# GateInterface.net
KiCad netlist of a schematic drawn in EAGLE
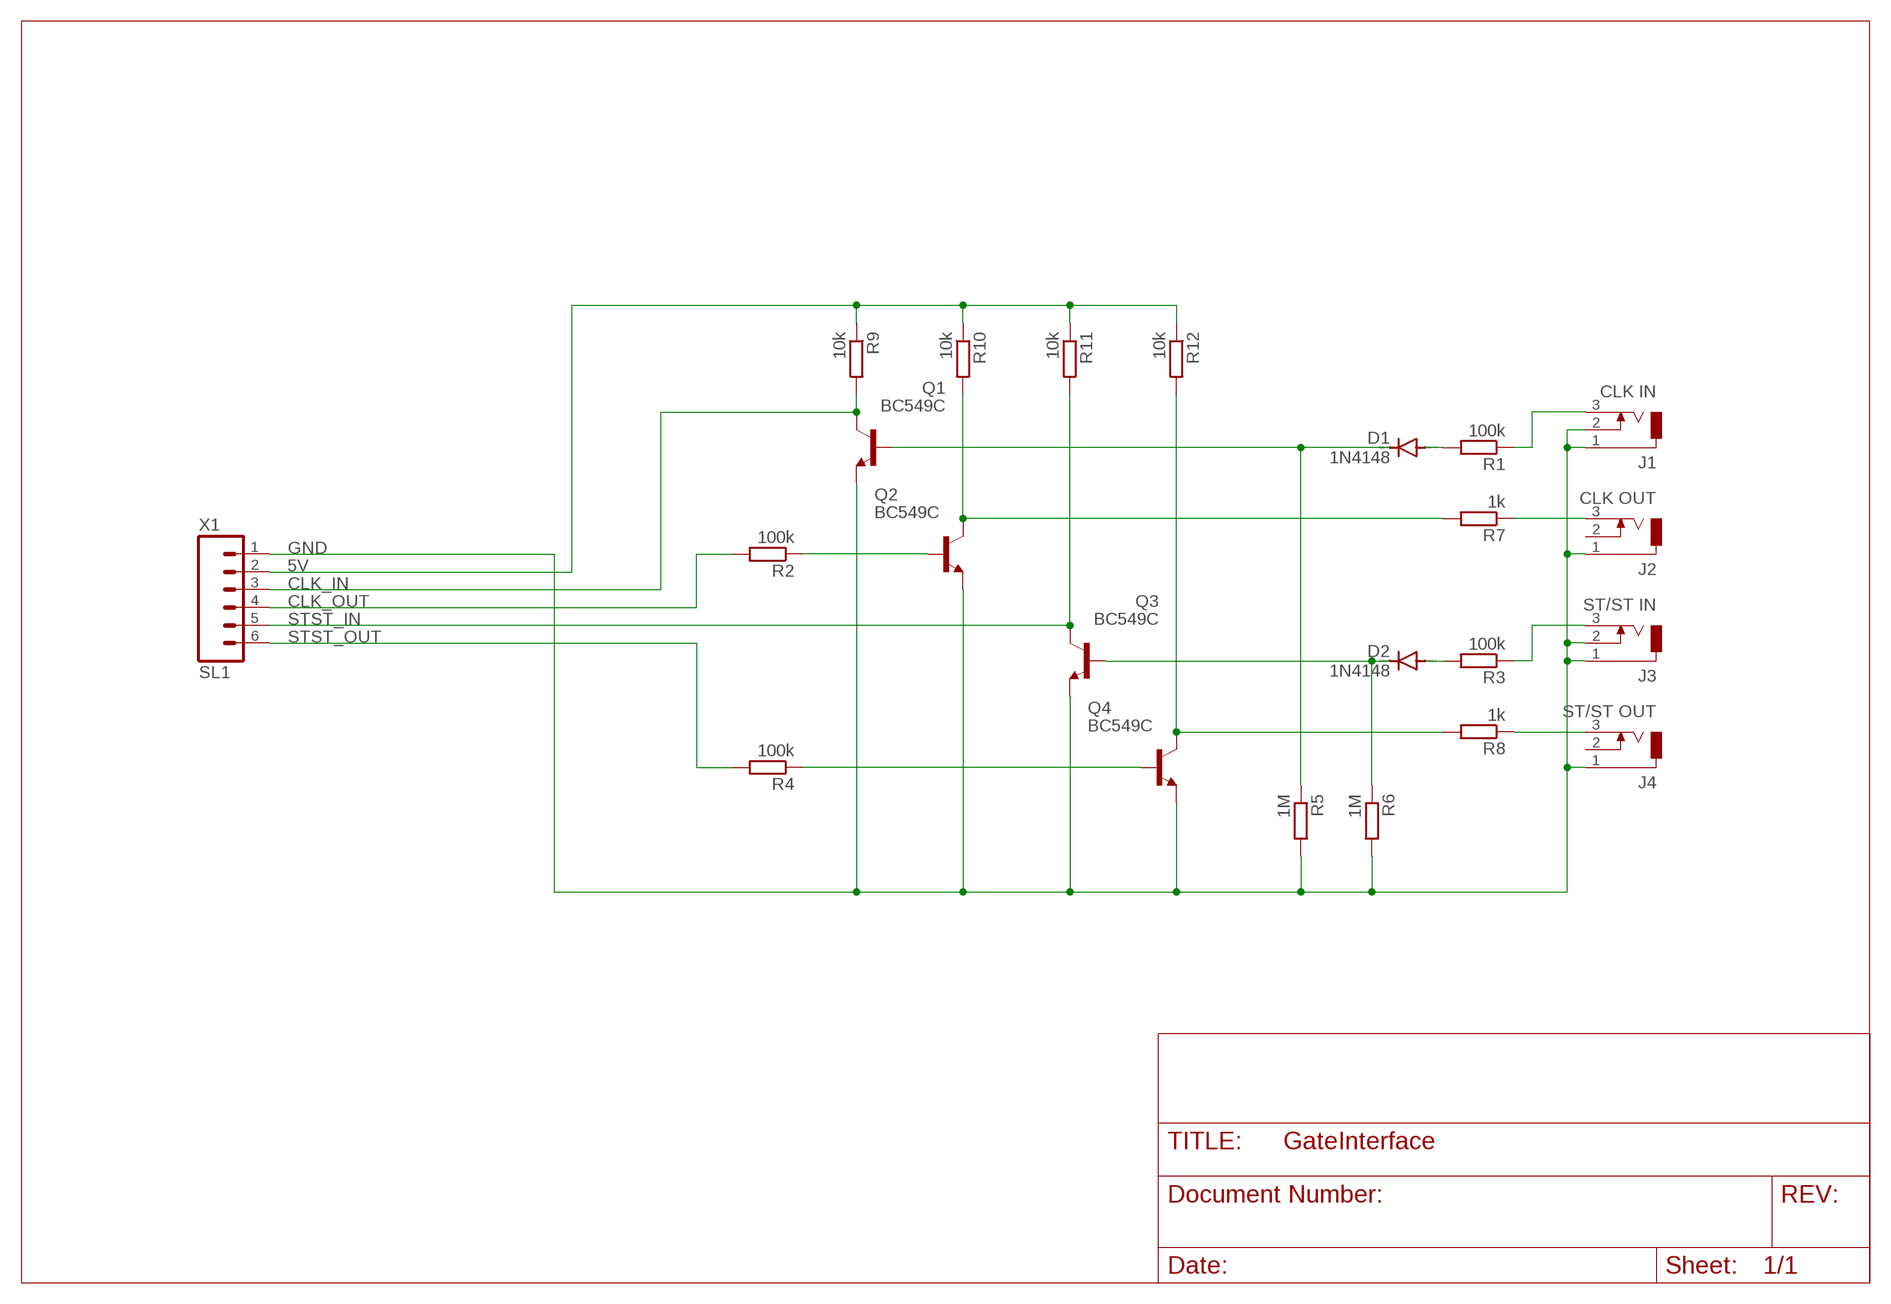
[diagram p0: schematic, sheet 1]

(export (version "E")
  (design (tool "Eeschema 10.0.6"))
  (components
    (comp (ref "D1")
      (value "1N4148")
      (footprint "eagle-import:DO35-10")
      (libsource (lib "eagle-import") (part "1N4148DO35-10"))
    )
    (comp (ref "D2")
      (value "1N4148")
      (footprint "eagle-import:DO35-10")
      (libsource (lib "eagle-import") (part "1N4148DO35-10"))
    )
    (comp (ref "J1")
      (value "CLK IN")
      (footprint "eagle-import:DCJ0202")
      (libsource (lib "eagle-import") (part "DCJ0202"))
    )
    (comp (ref "J2")
      (value "CLK OUT")
      (footprint "eagle-import:DCJ0202")
      (libsource (lib "eagle-import") (part "DCJ0202"))
    )
    (comp (ref "J3")
      (value "ST/ST IN")
      (footprint "eagle-import:DCJ0202")
      (libsource (lib "eagle-import") (part "DCJ0202"))
    )
    (comp (ref "J4")
      (value "ST/ST OUT")
      (footprint "eagle-import:DCJ0202")
      (libsource (lib "eagle-import") (part "DCJ0202"))
    )
    (comp (ref "Q1")
      (value "BC549C")
      (footprint "eagle-import:TO92-EBC")
      (libsource (lib "eagle-import") (part "BC549C"))
    )
    (comp (ref "Q2")
      (value "BC549C")
      (footprint "eagle-import:TO92-EBC")
      (libsource (lib "eagle-import") (part "BC549C"))
    )
    (comp (ref "Q3")
      (value "BC549C")
      (footprint "eagle-import:TO92-EBC")
      (libsource (lib "eagle-import") (part "BC549C"))
    )
    (comp (ref "Q4")
      (value "BC549C")
      (footprint "eagle-import:TO92-EBC")
      (libsource (lib "eagle-import") (part "BC549C"))
    )
    (comp (ref "R1")
      (value "100k")
      (footprint "eagle-import:0207_10")
      (libsource (lib "eagle-import") (part "R-EU_0207/10"))
    )
    (comp (ref "R2")
      (value "100k")
      (footprint "eagle-import:0207_10")
      (libsource (lib "eagle-import") (part "R-EU_0207/10"))
    )
    (comp (ref "R3")
      (value "100k")
      (footprint "eagle-import:0207_10")
      (libsource (lib "eagle-import") (part "R-EU_0207/10"))
    )
    (comp (ref "R4")
      (value "100k")
      (footprint "eagle-import:0207_10")
      (libsource (lib "eagle-import") (part "R-EU_0207/10"))
    )
    (comp (ref "R5")
      (value "1M")
      (footprint "eagle-import:0207_10")
      (libsource (lib "eagle-import") (part "R-EU_0207/10"))
    )
    (comp (ref "R6")
      (value "1M")
      (footprint "eagle-import:0207_10")
      (libsource (lib "eagle-import") (part "R-EU_0207/10"))
    )
    (comp (ref "R7")
      (value "1k")
      (footprint "eagle-import:0207_10")
      (libsource (lib "eagle-import") (part "R-EU_0207/10"))
    )
    (comp (ref "R8")
      (value "1k")
      (footprint "eagle-import:0207_10")
      (libsource (lib "eagle-import") (part "R-EU_0207/10"))
    )
    (comp (ref "R9")
      (value "10k")
      (footprint "eagle-import:0207_10")
      (libsource (lib "eagle-import") (part "R-EU_0207/10"))
    )
    (comp (ref "R10")
      (value "10k")
      (footprint "eagle-import:0207_10")
      (libsource (lib "eagle-import") (part "R-EU_0207/10"))
    )
    (comp (ref "R11")
      (value "10k")
      (footprint "eagle-import:0207_10")
      (libsource (lib "eagle-import") (part "R-EU_0207/10"))
    )
    (comp (ref "R12")
      (value "10k")
      (footprint "eagle-import:0207_10")
      (libsource (lib "eagle-import") (part "R-EU_0207/10"))
    )
    (comp (ref "SL1")
      (value "X1")
      (footprint "eagle-import:06P")
      (libsource (lib "eagle-import") (part "M06"))
    )
  )
  (nets
    (net (code "1") (name "/5V") (class "Default")
      (node (ref "R10") (pin "1") (pinfunction "1_1") (pintype "passive"))
      (node (ref "R11") (pin "1") (pinfunction "1_1") (pintype "passive"))
      (node (ref "R12") (pin "1") (pinfunction "1_1") (pintype "passive"))
      (node (ref "R9") (pin "1") (pinfunction "1_1") (pintype "passive"))
      (node (ref "SL1") (pin "2") (pinfunction "2_2") (pintype "passive"))
    )
    (net (code "2") (name "/CLK_IN") (class "Default")
      (node (ref "Q1") (pin "C") (pinfunction "C_C") (pintype "passive"))
      (node (ref "R9") (pin "2") (pinfunction "2_2") (pintype "passive"))
      (node (ref "SL1") (pin "3") (pinfunction "3_3") (pintype "passive"))
    )
    (net (code "3") (name "/CLK_OUT") (class "Default")
      (node (ref "R2") (pin "2") (pinfunction "2_2") (pintype "passive"))
      (node (ref "SL1") (pin "4") (pinfunction "4_4") (pintype "passive"))
    )
    (net (code "4") (name "/GND") (class "Default")
      (node (ref "J1") (pin "1") (pinfunction "1_1") (pintype "passive"))
      (node (ref "J1") (pin "2") (pinfunction "2_2") (pintype "passive"))
      (node (ref "J2") (pin "1") (pinfunction "1_1") (pintype "passive"))
      (node (ref "J3") (pin "1") (pinfunction "1_1") (pintype "passive"))
      (node (ref "J3") (pin "2") (pinfunction "2_2") (pintype "passive"))
      (node (ref "J4") (pin "1") (pinfunction "1_1") (pintype "passive"))
      (node (ref "Q1") (pin "E") (pinfunction "E_E") (pintype "passive"))
      (node (ref "Q2") (pin "E") (pinfunction "E_E") (pintype "passive"))
      (node (ref "Q3") (pin "E") (pinfunction "E_E") (pintype "passive"))
      (node (ref "Q4") (pin "E") (pinfunction "E_E") (pintype "passive"))
      (node (ref "R5") (pin "2") (pinfunction "2_2") (pintype "passive"))
      (node (ref "R6") (pin "2") (pinfunction "2_2") (pintype "passive"))
      (node (ref "SL1") (pin "1") (pinfunction "1_1") (pintype "passive"))
    )
    (net (code "5") (name "/STST_IN") (class "Default")
      (node (ref "Q3") (pin "C") (pinfunction "C_C") (pintype "passive"))
      (node (ref "R11") (pin "2") (pinfunction "2_2") (pintype "passive"))
      (node (ref "SL1") (pin "5") (pinfunction "5_5") (pintype "passive"))
    )
    (net (code "6") (name "/STST_OUT") (class "Default")
      (node (ref "R4") (pin "2") (pinfunction "2_2") (pintype "passive"))
      (node (ref "SL1") (pin "6") (pinfunction "6_6") (pintype "passive"))
    )
    (net (code "7") (name "Net-(D1-PadA)") (class "Default")
      (node (ref "D1") (pin "A") (pinfunction "A_A") (pintype "passive"))
      (node (ref "R1") (pin "2") (pinfunction "2_2") (pintype "passive"))
    )
    (net (code "8") (name "Net-(D1-PadC)") (class "Default")
      (node (ref "D1") (pin "C") (pinfunction "C_C") (pintype "passive"))
      (node (ref "Q1") (pin "B") (pinfunction "B_B") (pintype "passive"))
      (node (ref "R5") (pin "1") (pinfunction "1_1") (pintype "passive"))
    )
    (net (code "9") (name "Net-(D2-PadA)") (class "Default")
      (node (ref "D2") (pin "A") (pinfunction "A_A") (pintype "passive"))
      (node (ref "R3") (pin "2") (pinfunction "2_2") (pintype "passive"))
    )
    (net (code "10") (name "Net-(D2-PadC)") (class "Default")
      (node (ref "D2") (pin "C") (pinfunction "C_C") (pintype "passive"))
      (node (ref "Q3") (pin "B") (pinfunction "B_B") (pintype "passive"))
      (node (ref "R6") (pin "1") (pinfunction "1_1") (pintype "passive"))
    )
    (net (code "11") (name "Net-(J1-Pad3)") (class "Default")
      (node (ref "J1") (pin "3") (pinfunction "3_3") (pintype "passive"))
      (node (ref "R1") (pin "1") (pinfunction "1_1") (pintype "passive"))
    )
    (net (code "12") (name "Net-(J2-Pad3)") (class "Default")
      (node (ref "J2") (pin "3") (pinfunction "3_3") (pintype "passive"))
      (node (ref "R7") (pin "1") (pinfunction "1_1") (pintype "passive"))
    )
    (net (code "13") (name "Net-(J3-Pad3)") (class "Default")
      (node (ref "J3") (pin "3") (pinfunction "3_3") (pintype "passive"))
      (node (ref "R3") (pin "1") (pinfunction "1_1") (pintype "passive"))
    )
    (net (code "14") (name "Net-(J4-Pad3)") (class "Default")
      (node (ref "J4") (pin "3") (pinfunction "3_3") (pintype "passive"))
      (node (ref "R8") (pin "1") (pinfunction "1_1") (pintype "passive"))
    )
    (net (code "15") (name "Net-(Q2-PadB)") (class "Default")
      (node (ref "Q2") (pin "B") (pinfunction "B_B") (pintype "passive"))
      (node (ref "R2") (pin "1") (pinfunction "1_1") (pintype "passive"))
    )
    (net (code "16") (name "Net-(Q2-PadC)") (class "Default")
      (node (ref "Q2") (pin "C") (pinfunction "C_C") (pintype "passive"))
      (node (ref "R10") (pin "2") (pinfunction "2_2") (pintype "passive"))
      (node (ref "R7") (pin "2") (pinfunction "2_2") (pintype "passive"))
    )
    (net (code "17") (name "Net-(Q4-PadB)") (class "Default")
      (node (ref "Q4") (pin "B") (pinfunction "B_B") (pintype "passive"))
      (node (ref "R4") (pin "1") (pinfunction "1_1") (pintype "passive"))
    )
    (net (code "18") (name "Net-(Q4-PadC)") (class "Default")
      (node (ref "Q4") (pin "C") (pinfunction "C_C") (pintype "passive"))
      (node (ref "R12") (pin "2") (pinfunction "2_2") (pintype "passive"))
      (node (ref "R8") (pin "2") (pinfunction "2_2") (pintype "passive"))
    )
    (net (code "19") (name "unconnected-(J2-Pad2)") (class "Default")
      (node (ref "J2") (pin "2") (pinfunction "2_2") (pintype "passive"))
    )
    (net (code "20") (name "unconnected-(J4-Pad2)") (class "Default")
      (node (ref "J4") (pin "2") (pinfunction "2_2") (pintype "passive"))
    )
  )
)
